# usb_plug.net
KiCad netlist of a schematic drawn in Altium Designer
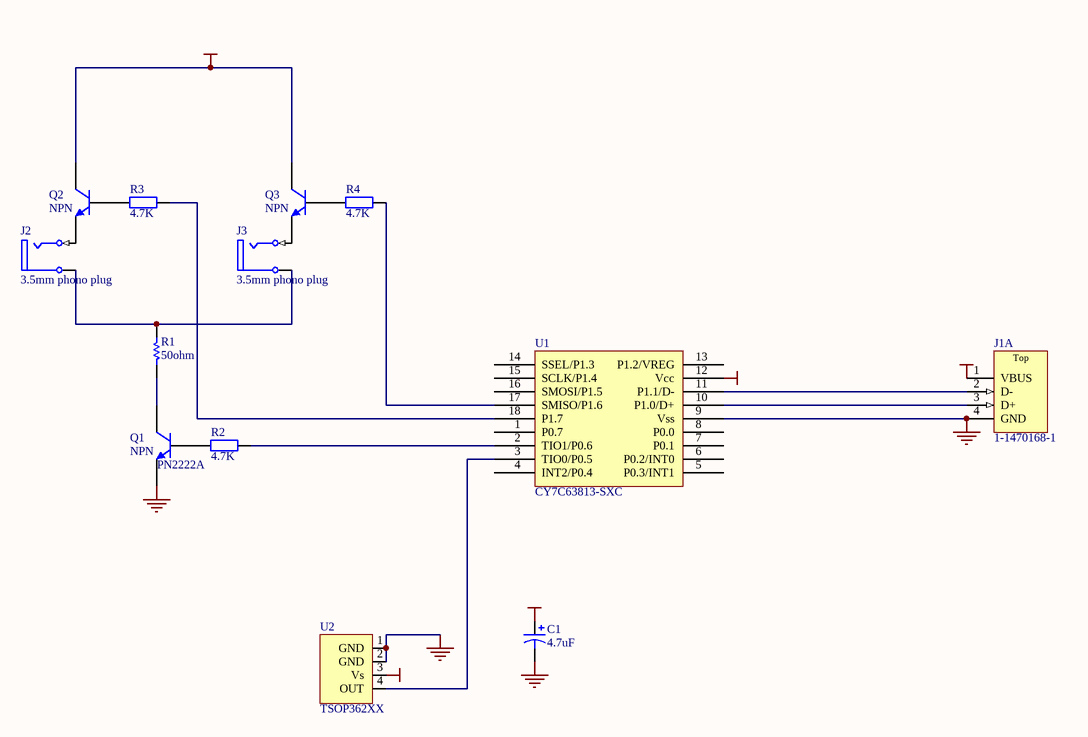
[diagram p0: usb_plug.SCHDOC]

(export (version "E")
  (design (tool "Eeschema 10.0.6"))
  (components
    (comp (ref "C1")
      (value "4.7uF")
      (footprint "TC3216-1206")
      (description "Polarized Capacitor (Radial)")
      (fields (field (name "Comment") "Cap Pol1") (field (name "PUBLISHER") "Altium Limited"))
      (libsource (lib "Miscellaneous Devices") (part "Cap Pol1"))
    )
    (comp (ref "J1")
      (value "1-1470168-1")
      (footprint "1470695")
      (description "USB 1.1, Right Angle, Thru-Hole, A Type, Receptacle, 4x4 Position, Stacked, Black")
      (fields (field (name "PUBLISHER") "Altium Limited"))
      (libsource (lib "AMP Serial Bus USB") (part "1-1470168-1"))
    )
    (comp (ref "J2")
      (value "3.5mm phono plug")
      (footprint "CUI MJ-3523-SMT")
      (description "Jack Socket, 1/4\" [6.5mm], Thru-Hole, Vertical, 2-Conductor Open Circuit")
      (fields (field (name "PUBLISHER") "Altium Limited"))
      (libsource (lib "Miscellaneous Connectors") (part "Phonejack2"))
    )
    (comp (ref "J3")
      (value "3.5mm phono plug")
      (footprint "CUI MJ-3523-SMT")
      (description "Jack Socket, 1/4\" [6.5mm], Thru-Hole, Vertical, 2-Conductor Open Circuit")
      (fields (field (name "PUBLISHER") "Altium Limited"))
      (libsource (lib "Miscellaneous Connectors") (part "Phonejack2"))
    )
    (comp (ref "Q1")
      (value "NPN")
      (footprint "SO-G3/D4.1")
      (description "NPN Bipolar Transistor")
      (fields (field (name "PUBLISHER") "Altium Limited"))
      (libsource (lib "Miscellaneous Devices") (part "NPN"))
    )
    (comp (ref "Q2")
      (value "NPN")
      (footprint "SO-G3/D4.1")
      (description "NPN Bipolar Transistor")
      (fields (field (name "PUBLISHER") "Altium Limited"))
      (libsource (lib "Miscellaneous Devices") (part "NPN"))
    )
    (comp (ref "Q3")
      (value "NPN")
      (footprint "SO-G3/D4.1")
      (description "NPN Bipolar Transistor")
      (fields (field (name "PUBLISHER") "Altium Limited"))
      (libsource (lib "Miscellaneous Devices") (part "NPN"))
    )
    (comp (ref "R1")
      (value "50ohm")
      (footprint "CR1608-0603")
      (description "Semiconductor Resistor")
      (fields (field (name "PUBLISHER") "Altium Limited"))
      (libsource (lib "Miscellaneous Devices") (part "Res Semi"))
    )
    (comp (ref "R2")
      (value "4.7K")
      (footprint "CR1608-0603")
      (description "Resistor")
      (fields (field (name "Comment") "Res2") (field (name "PUBLISHER") "Altium Limited"))
      (libsource (lib "Miscellaneous Devices") (part "Res2"))
    )
    (comp (ref "R3")
      (value "4.7K")
      (footprint "CR1608-0603")
      (description "Resistor")
      (fields (field (name "Comment") "Res2") (field (name "PUBLISHER") "Altium Limited"))
      (libsource (lib "Miscellaneous Devices") (part "Res2"))
    )
    (comp (ref "R4")
      (value "4.7K")
      (footprint "CR1608-0603")
      (description "Resistor")
      (fields (field (name "Comment") "Res2") (field (name "PUBLISHER") "Altium Limited"))
      (libsource (lib "Miscellaneous Devices") (part "Res2"))
    )
    (comp (ref "U1")
      (value "CY7C63813-SXC")
      (footprint "SO-G18/E6.2")
      (description "USB microcontroller, SMT")
      (libsource (lib "ir") (part "CY7C63813-SXC"))
    )
    (comp (ref "U2") (value "TSOP362XX") (footprint "TSOP 362XX") (libsource (lib "ir") (part "TSOP36238")))
  )
  (nets
    (net (code "1") (name "GND") (class "Default")
      (node (ref "C1") (pin "2") (pinfunction "2_2") (pintype "passive"))
      (node (ref "J1") (pin "4") (pinfunction "GND_4") (pintype "power_in"))
      (node (ref "Q1") (pin "3") (pinfunction "E_3") (pintype "passive"))
      (node (ref "U1") (pin "9") (pinfunction "Vss_9") (pintype "passive"))
      (node (ref "U2") (pin "1") (pinfunction "GND_1") (pintype "passive"))
      (node (ref "U2") (pin "2") (pinfunction "GND_2") (pintype "passive"))
    )
    (net (code "2") (name "Net-(J1A-D+)") (class "Default")
      (node (ref "J1") (pin "3") (pinfunction "D+_3") (pintype "input"))
      (node (ref "U1") (pin "10") (pinfunction "P1.0/D+_10") (pintype "passive"))
    )
    (net (code "3") (name "Net-(J1A-D-)") (class "Default")
      (node (ref "J1") (pin "2") (pinfunction "D-_2") (pintype "input"))
      (node (ref "U1") (pin "11") (pinfunction "P1.1/D-_11") (pintype "passive"))
    )
    (net (code "4") (name "Net-(J2-S)") (class "Default")
      (node (ref "J2") (pin "5") (pinfunction "S_5") (pintype "power_in"))
      (node (ref "J3") (pin "5") (pinfunction "S_5") (pintype "power_in"))
      (node (ref "R1") (pin "2") (pinfunction "2_2") (pintype "passive"))
    )
    (net (code "5") (name "Net-(J2-T)") (class "Default")
      (node (ref "J2") (pin "1") (pinfunction "T_1") (pintype "input"))
      (node (ref "Q2") (pin "3") (pinfunction "E_3") (pintype "passive"))
    )
    (net (code "6") (name "Net-(J3-T)") (class "Default")
      (node (ref "J3") (pin "1") (pinfunction "T_1") (pintype "input"))
      (node (ref "Q3") (pin "3") (pinfunction "E_3") (pintype "passive"))
    )
    (net (code "7") (name "Net-(Q1-B)") (class "Default")
      (node (ref "Q1") (pin "2") (pinfunction "B_2") (pintype "passive"))
      (node (ref "R2") (pin "2") (pinfunction "2_2") (pintype "passive"))
    )
    (net (code "8") (name "Net-(Q1-C)") (class "Default")
      (node (ref "Q1") (pin "1") (pinfunction "C_1") (pintype "passive"))
      (node (ref "R1") (pin "1") (pinfunction "1_1") (pintype "passive"))
    )
    (net (code "9") (name "Net-(Q2-B)") (class "Default")
      (node (ref "Q2") (pin "2") (pinfunction "B_2") (pintype "passive"))
      (node (ref "R3") (pin "2") (pinfunction "2_2") (pintype "passive"))
    )
    (net (code "10") (name "Net-(Q3-B)") (class "Default")
      (node (ref "Q3") (pin "2") (pinfunction "B_2") (pintype "passive"))
      (node (ref "R4") (pin "2") (pinfunction "2_2") (pintype "passive"))
    )
    (net (code "11") (name "Net-(U1-P1.7)") (class "Default")
      (node (ref "R3") (pin "1") (pinfunction "1_1") (pintype "passive"))
      (node (ref "U1") (pin "18") (pinfunction "P1.7_18") (pintype "passive"))
    )
    (net (code "12") (name "Net-(U1-SMISO{slash}P1.6)") (class "Default")
      (node (ref "R4") (pin "1") (pinfunction "1_1") (pintype "passive"))
      (node (ref "U1") (pin "17") (pinfunction "SMISO/P1.6_17") (pintype "passive"))
    )
    (net (code "13") (name "Net-(U1-TIO0{slash}P0.5)") (class "Default")
      (node (ref "U1") (pin "3") (pinfunction "TIO0/P0.5_3") (pintype "passive"))
      (node (ref "U2") (pin "4") (pinfunction "OUT_4") (pintype "passive"))
    )
    (net (code "14") (name "Net-(U1-TIO1{slash}P0.6)") (class "Default")
      (node (ref "R2") (pin "1") (pinfunction "1_1") (pintype "passive"))
      (node (ref "U1") (pin "2") (pinfunction "TIO1/P0.6_2") (pintype "passive"))
    )
    (net (code "15") (name "VCC") (class "Default")
      (node (ref "C1") (pin "1") (pinfunction "1_1") (pintype "passive"))
      (node (ref "J1") (pin "1") (pinfunction "VBUS_1") (pintype "power_in"))
      (node (ref "Q2") (pin "1") (pinfunction "C_1") (pintype "passive"))
      (node (ref "Q3") (pin "1") (pinfunction "C_1") (pintype "passive"))
      (node (ref "U1") (pin "12") (pinfunction "Vcc_12") (pintype "passive"))
      (node (ref "U2") (pin "3") (pinfunction "Vs_3") (pintype "passive"))
    )
    (net (code "16") (name "unconnected-(U1-INT2{slash}P0.4-Pad4)") (class "Default")
      (node (ref "U1") (pin "4") (pinfunction "INT2/P0.4_4") (pintype "passive"))
    )
    (net (code "17") (name "unconnected-(U1-P0.0-Pad8)") (class "Default")
      (node (ref "U1") (pin "8") (pinfunction "P0.0_8") (pintype "passive"))
    )
    (net (code "18") (name "unconnected-(U1-P0.1-Pad7)") (class "Default")
      (node (ref "U1") (pin "7") (pinfunction "P0.1_7") (pintype "passive"))
    )
    (net (code "19") (name "unconnected-(U1-P0.2{slash}INT0-Pad6)") (class "Default")
      (node (ref "U1") (pin "6") (pinfunction "P0.2/INT0_6") (pintype "passive"))
    )
    (net (code "20") (name "unconnected-(U1-P0.3{slash}INT1-Pad5)") (class "Default")
      (node (ref "U1") (pin "5") (pinfunction "P0.3/INT1_5") (pintype "passive"))
    )
    (net (code "21") (name "unconnected-(U1-P0.7-Pad1)") (class "Default")
      (node (ref "U1") (pin "1") (pinfunction "P0.7_1") (pintype "passive"))
    )
    (net (code "22") (name "unconnected-(U1-P1.2{slash}VREG-Pad13)") (class "Default")
      (node (ref "U1") (pin "13") (pinfunction "P1.2/VREG_13") (pintype "passive"))
    )
    (net (code "23") (name "unconnected-(U1-SCLK{slash}P1.4-Pad15)") (class "Default")
      (node (ref "U1") (pin "15") (pinfunction "SCLK/P1.4_15") (pintype "passive"))
    )
    (net (code "24") (name "unconnected-(U1-SMOSI{slash}P1.5-Pad16)") (class "Default")
      (node (ref "U1") (pin "16") (pinfunction "SMOSI/P1.5_16") (pintype "passive"))
    )
    (net (code "25") (name "unconnected-(U1-SSEL{slash}P1.3-Pad14)") (class "Default")
      (node (ref "U1") (pin "14") (pinfunction "SSEL/P1.3_14") (pintype "passive"))
    )
  )
)
